# FIDO2AUTH_001.net
KiCad netlist of a schematic drawn in EAGLE
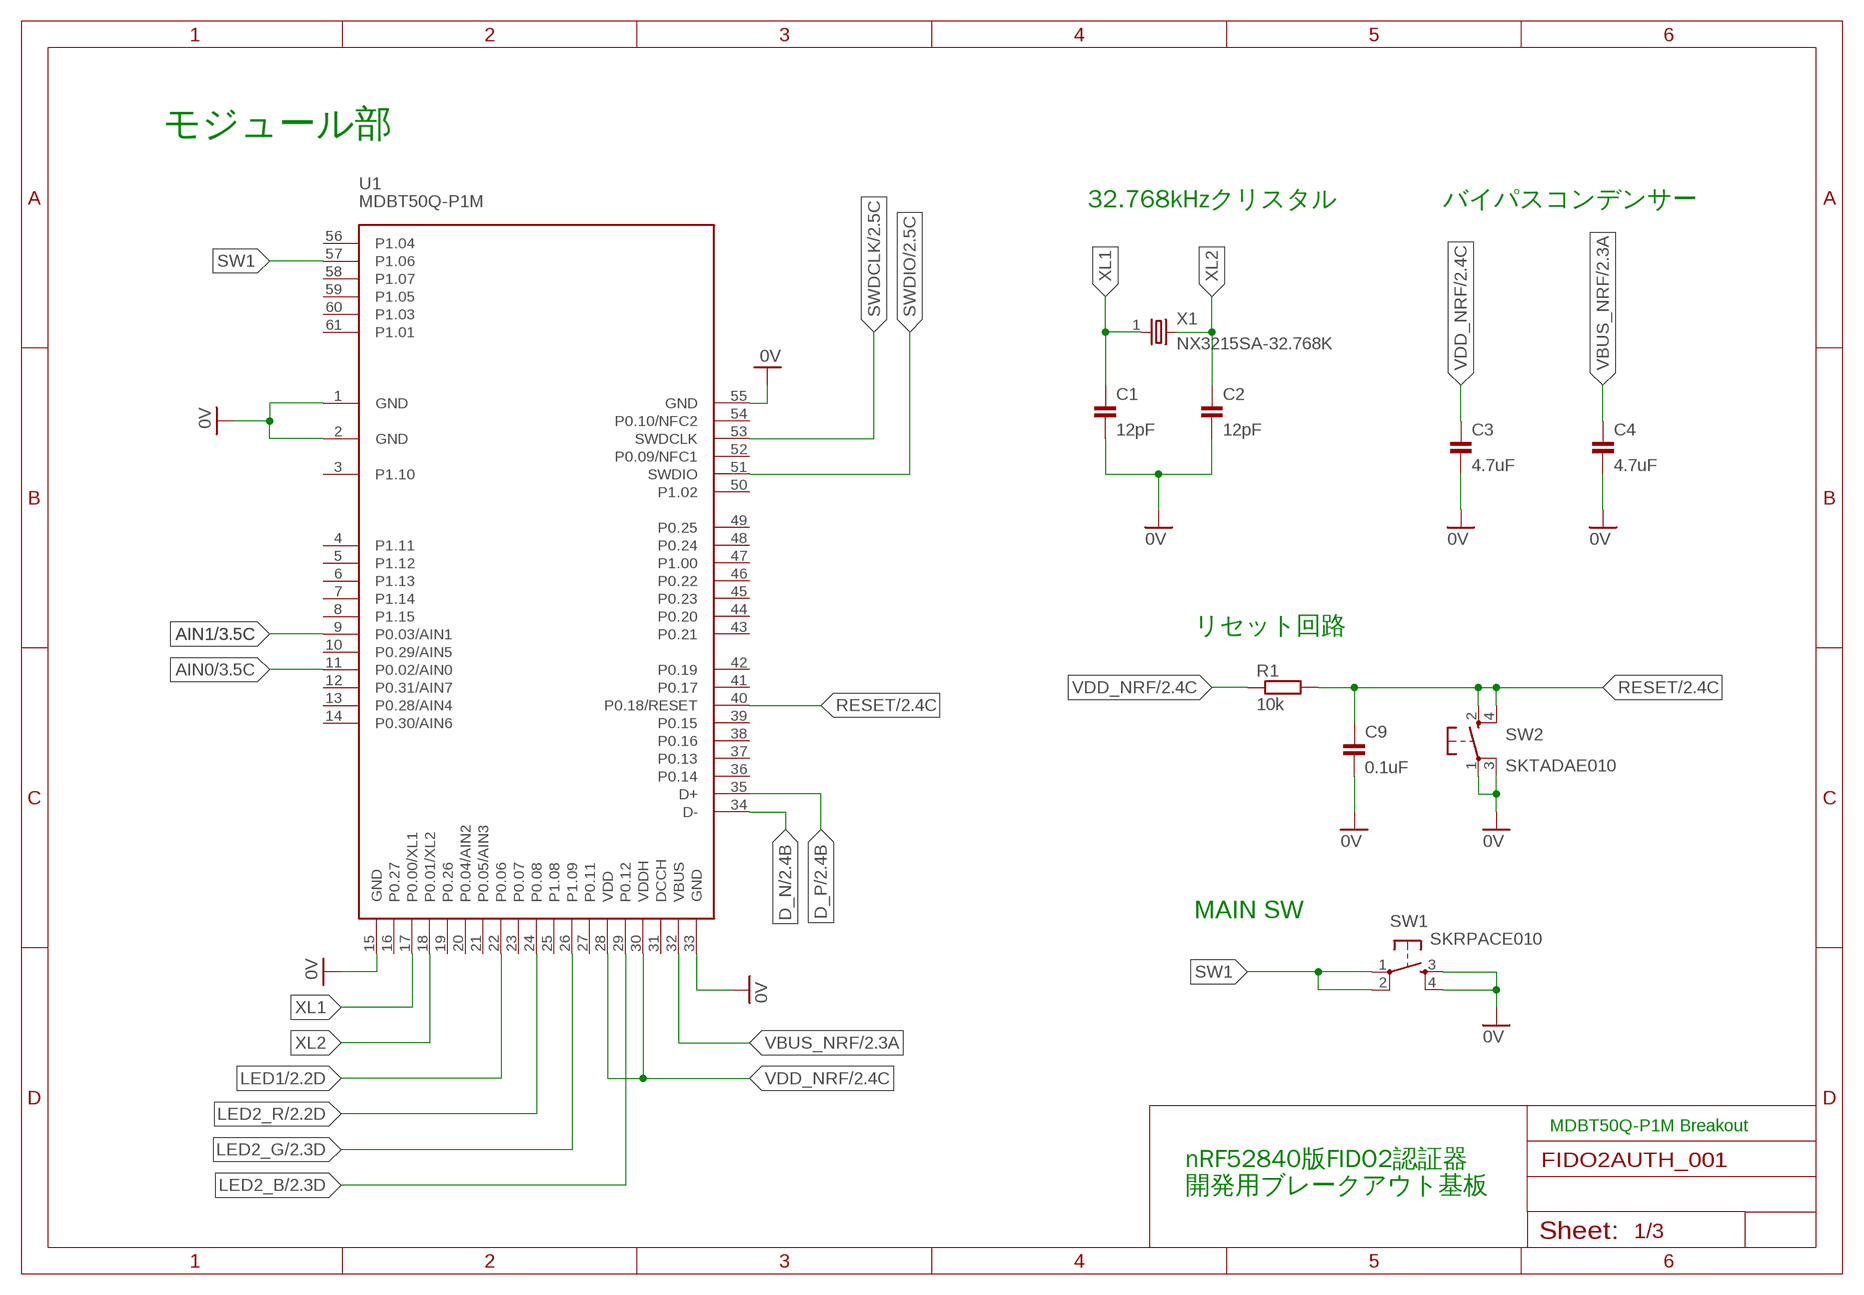
[diagram p0: schematic, sheet 1]
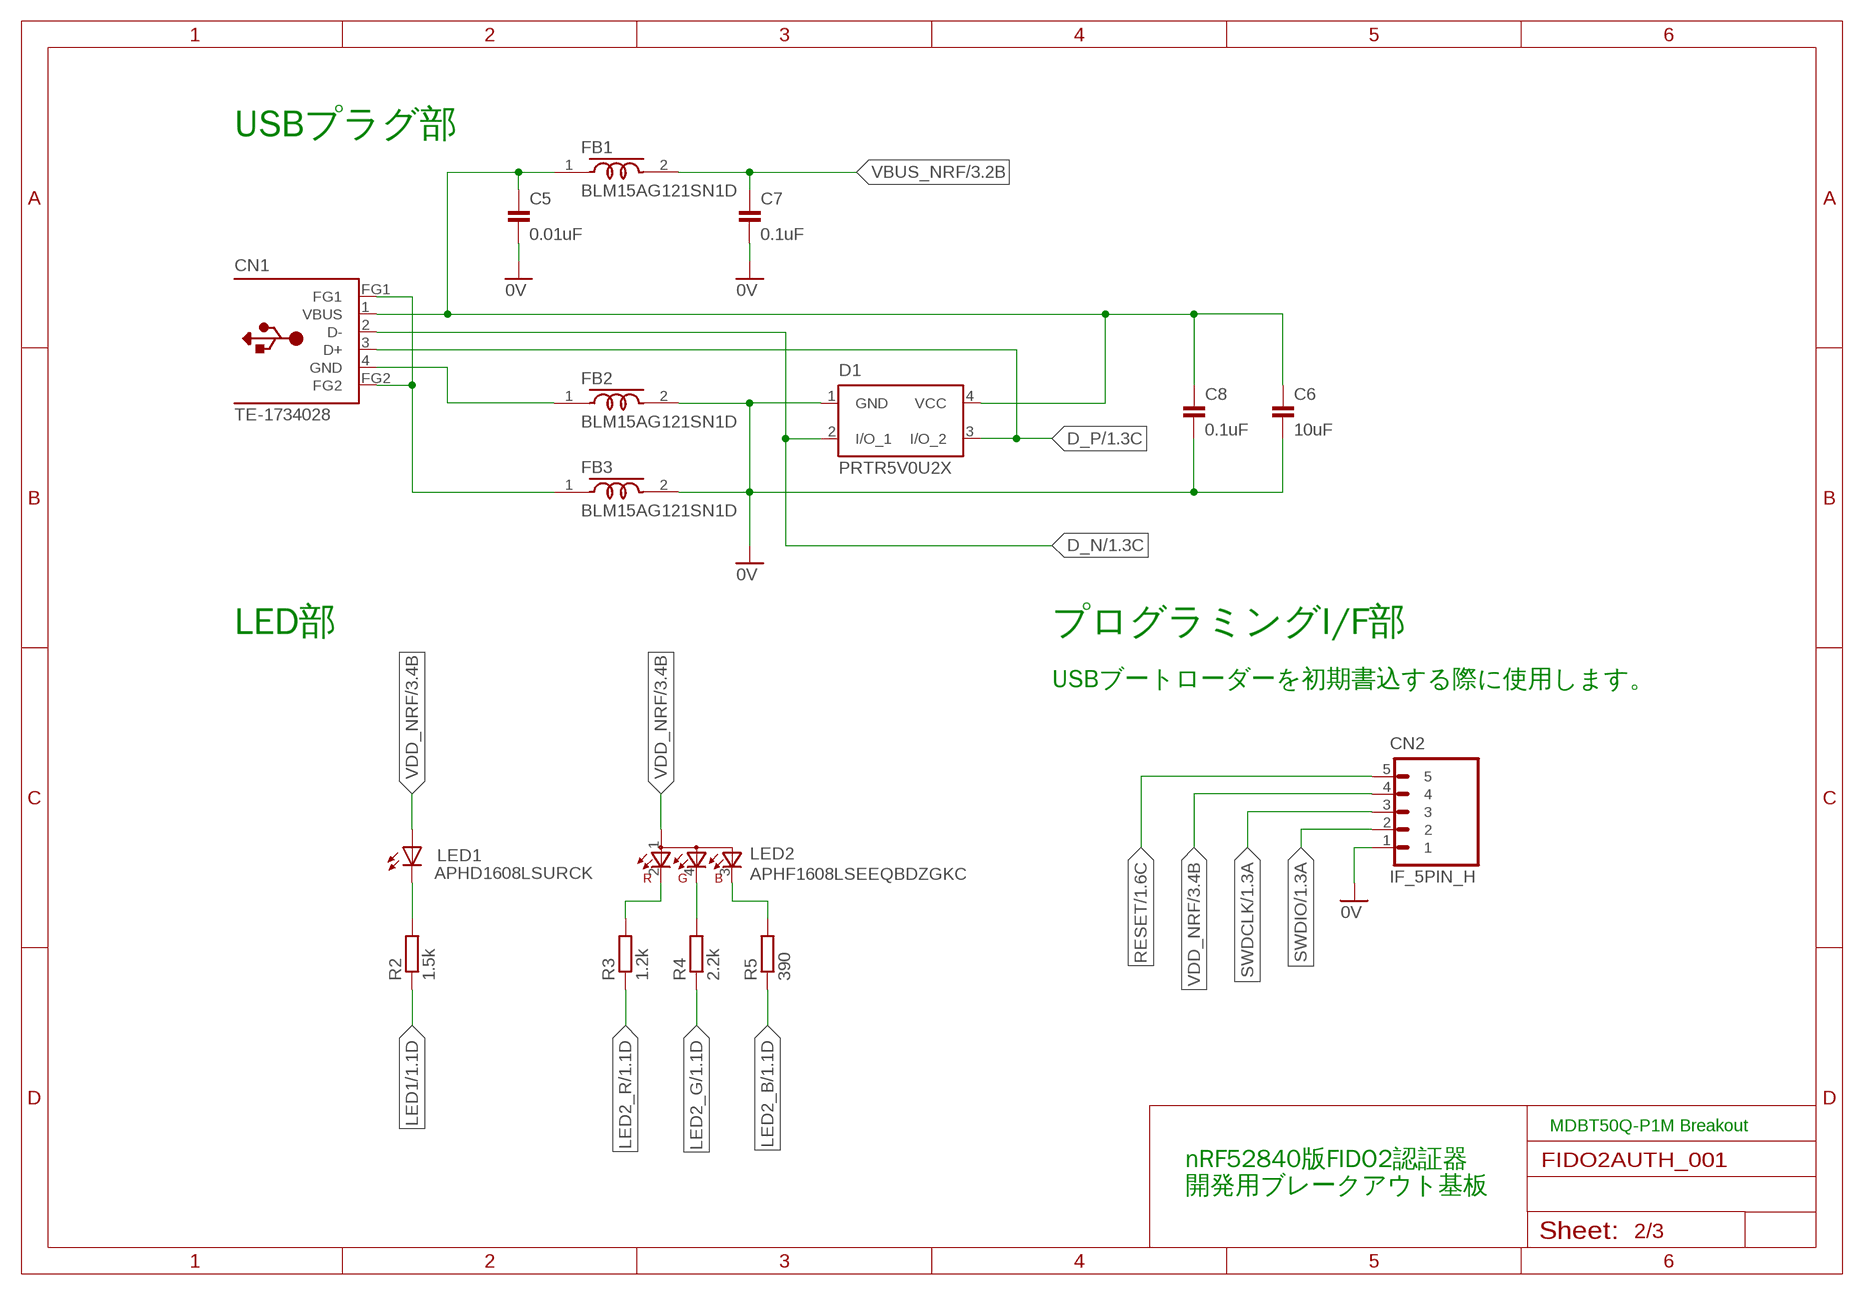
[diagram p1: schematic, sheet 2]
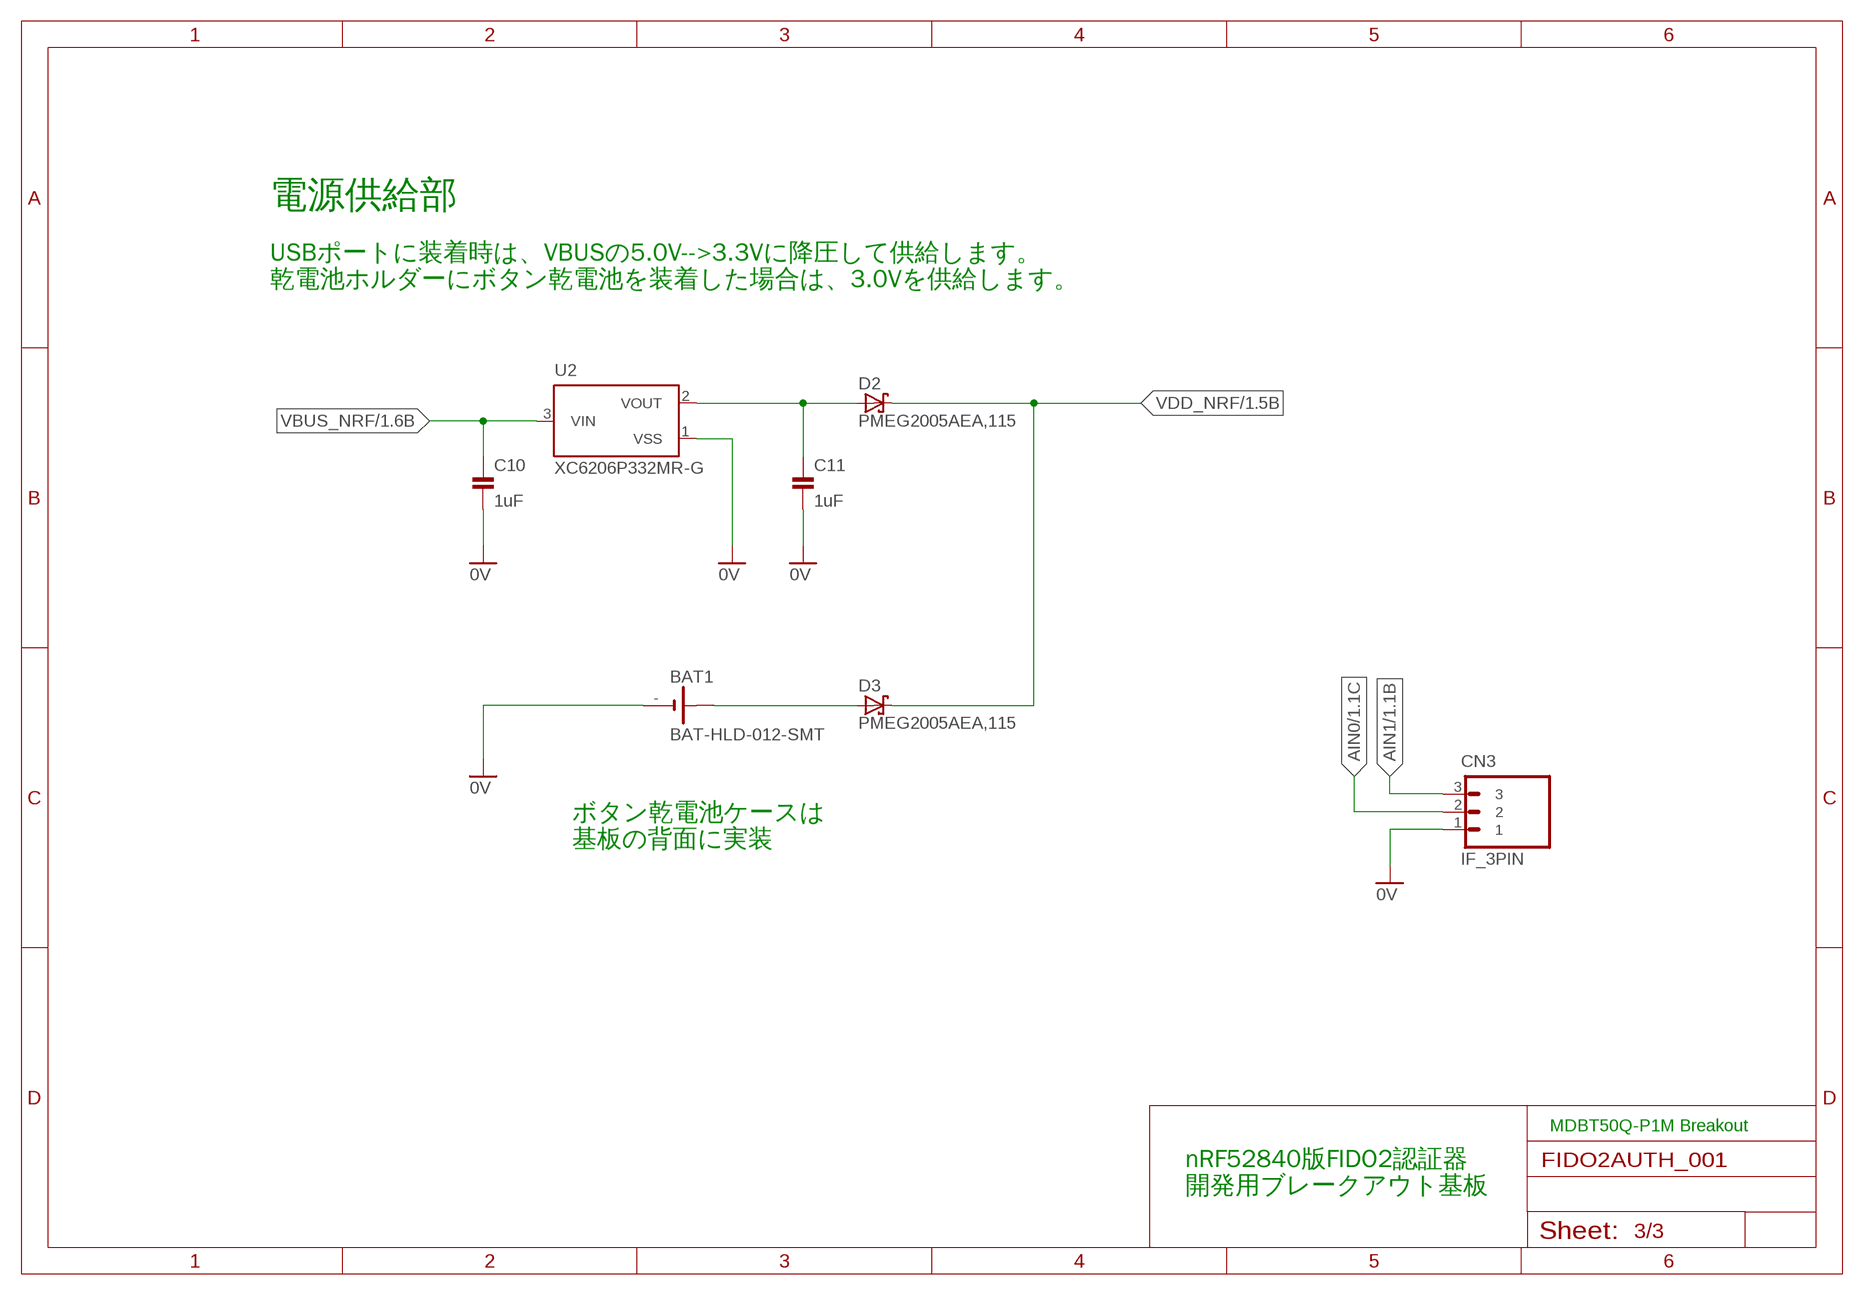
[diagram p2: schematic, sheet 3]

(export (version "E")
  (design (tool "Eeschema 10.0.6"))
  (components
    (comp (ref "C1")
      (value "12pF")
      (footprint "eagle-import:C0603K")
      (libsource (lib "eagle-import") (part "CAP_0603"))
    )
    (comp (ref "C2")
      (value "12pF")
      (footprint "eagle-import:C0603K")
      (libsource (lib "eagle-import") (part "CAP_0603"))
    )
    (comp (ref "C3")
      (value "4.7uF")
      (footprint "eagle-import:C0603K")
      (libsource (lib "eagle-import") (part "CAP_0603"))
    )
    (comp (ref "C4")
      (value "4.7uF")
      (footprint "eagle-import:C0603K")
      (libsource (lib "eagle-import") (part "CAP_0603"))
    )
    (comp (ref "C9")
      (value "0.1uF")
      (footprint "eagle-import:C0603K")
      (libsource (lib "eagle-import") (part "CAP_0603"))
    )
    (comp (ref "R1")
      (value "10k")
      (footprint "eagle-import:R0603")
      (libsource (lib "eagle-import") (part "RESISTOR_0603"))
    )
    (comp (ref "SW1")
      (value "SKRPACE010")
      (footprint "eagle-import:SKRPACE010")
      (libsource (lib "eagle-import") (part "SKRPACE010"))
    )
    (comp (ref "SW2")
      (value "SKTADAE010")
      (footprint "eagle-import:SKTADAE010")
      (libsource (lib "eagle-import") (part "SKTADAE010"))
    )
    (comp (ref "U1")
      (value "MDBT50Q-P1M")
      (footprint "eagle-import:MDBT50Q-P1M")
      (libsource (lib "eagle-import") (part "MDBT50Q-P1M"))
    )
    (comp (ref "X1")
      (value "NX3215SA-32.768K")
      (footprint "eagle-import:NX3215")
      (libsource (lib "eagle-import") (part "NX3215SA-32.768K"))
    )
    (comp (ref "BAT1")
      (value "BAT-HLD-012-SMT")
      (footprint "eagle-import:BAT-HLD-012-SMT")
      (libsource (lib "eagle-import") (part "BAT-HLD-012-SMT"))
    )
    (comp (ref "C10")
      (value "1uF")
      (footprint "eagle-import:C0603K")
      (libsource (lib "eagle-import") (part "CAP_0603"))
    )
    (comp (ref "C11")
      (value "1uF")
      (footprint "eagle-import:C0603K")
      (libsource (lib "eagle-import") (part "CAP_0603"))
    )
    (comp (ref "CN3")
      (value "IF_3PIN")
      (footprint "eagle-import:HEADER_3PIN")
      (libsource (lib "eagle-import") (part "IF_3PIN"))
    )
    (comp (ref "D2")
      (value "PMEG2005AEA,115")
      (footprint "eagle-import:SOD323-W")
      (libsource (lib "eagle-import") (part "PMEG2005AEA,115"))
    )
    (comp (ref "D3")
      (value "PMEG2005AEA,115")
      (footprint "eagle-import:SOD323-W")
      (libsource (lib "eagle-import") (part "PMEG2005AEA,115"))
    )
    (comp (ref "U2")
      (value "XC6206P332MR-G")
      (footprint "eagle-import:SOT23")
      (libsource (lib "eagle-import") (part "XC6206P332MR-G"))
    )
    (comp (ref "C5")
      (value "0.01uF")
      (footprint "eagle-import:C0603K")
      (libsource (lib "eagle-import") (part "CAP_0603"))
    )
    (comp (ref "C6")
      (value "10uF")
      (footprint "eagle-import:C0603K")
      (libsource (lib "eagle-import") (part "CAP_0603"))
    )
    (comp (ref "C7")
      (value "0.1uF")
      (footprint "eagle-import:C0603K")
      (libsource (lib "eagle-import") (part "CAP_0603"))
    )
    (comp (ref "C8")
      (value "0.1uF")
      (footprint "eagle-import:C0603K")
      (libsource (lib "eagle-import") (part "CAP_0603"))
    )
    (comp (ref "CN1")
      (value "TE-1734028")
      (footprint "eagle-import:TE-1734028")
      (libsource (lib "eagle-import") (part "TE-1734028"))
    )
    (comp (ref "CN2")
      (value "IF_5PIN_H")
      (footprint "eagle-import:HEADER_5PIN")
      (libsource (lib "eagle-import") (part "IF_5PIN_H"))
    )
    (comp (ref "D1")
      (value "PRTR5V0U2X")
      (footprint "eagle-import:SOT143B")
      (libsource (lib "eagle-import") (part "PRTR5V0U2X"))
    )
    (comp (ref "FB1")
      (value "BLM15AG121SN1D")
      (footprint "eagle-import:C0402K@1")
      (libsource (lib "eagle-import") (part "BLM15AG121SN1D"))
    )
    (comp (ref "FB2")
      (value "BLM15AG121SN1D")
      (footprint "eagle-import:C0402K@1")
      (libsource (lib "eagle-import") (part "BLM15AG121SN1D"))
    )
    (comp (ref "FB3")
      (value "BLM15AG121SN1D")
      (footprint "eagle-import:C0402K@1")
      (libsource (lib "eagle-import") (part "BLM15AG121SN1D"))
    )
    (comp (ref "LED1")
      (value "APHD1608LSURCK")
      (footprint "eagle-import:CHIPLED_0603")
      (libsource (lib "eagle-import") (part "APHD1608LSURCK"))
    )
    (comp (ref "LED2")
      (value "APHF1608LSEEQBDZGKC")
      (footprint "eagle-import:APHF1608LSEEQBDZGKC")
      (libsource (lib "eagle-import") (part "APHF1608LSEEQBDZGKC"))
    )
    (comp (ref "R2")
      (value "1.5k")
      (footprint "eagle-import:R0603")
      (libsource (lib "eagle-import") (part "RESISTOR_0603"))
    )
    (comp (ref "R3")
      (value "1.2k")
      (footprint "eagle-import:R0603")
      (libsource (lib "eagle-import") (part "RESISTOR_0603"))
    )
    (comp (ref "R4")
      (value "2.2k")
      (footprint "eagle-import:R0603")
      (libsource (lib "eagle-import") (part "RESISTOR_0603"))
    )
    (comp (ref "R5")
      (value "390")
      (footprint "eagle-import:R0603")
      (libsource (lib "eagle-import") (part "RESISTOR_0603"))
    )
  )
  (nets
    (net (code "1") (name "0V") (class "Default")
      (node (ref "BAT1") (pin "-") (pinfunction "-_-") (pintype "passive"))
      (node (ref "C1") (pin "2") (pinfunction "2_2") (pintype "passive"))
      (node (ref "C10") (pin "2") (pinfunction "2_2") (pintype "passive"))
      (node (ref "C11") (pin "2") (pinfunction "2_2") (pintype "passive"))
      (node (ref "C2") (pin "2") (pinfunction "2_2") (pintype "passive"))
      (node (ref "C3") (pin "2") (pinfunction "2_2") (pintype "passive"))
      (node (ref "C4") (pin "2") (pinfunction "2_2") (pintype "passive"))
      (node (ref "C5") (pin "2") (pinfunction "2_2") (pintype "passive"))
      (node (ref "C6") (pin "2") (pinfunction "2_2") (pintype "passive"))
      (node (ref "C7") (pin "2") (pinfunction "2_2") (pintype "passive"))
      (node (ref "C8") (pin "2") (pinfunction "2_2") (pintype "passive"))
      (node (ref "C9") (pin "2") (pinfunction "2_2") (pintype "passive"))
      (node (ref "CN2") (pin "1") (pinfunction "1_1") (pintype "passive"))
      (node (ref "CN3") (pin "1") (pinfunction "1_1") (pintype "passive"))
      (node (ref "D1") (pin "1") (pinfunction "GND_1") (pintype "passive"))
      (node (ref "FB2") (pin "2") (pinfunction "2_2") (pintype "passive"))
      (node (ref "FB3") (pin "2") (pinfunction "2_2") (pintype "passive"))
      (node (ref "SW1") (pin "3") (pinfunction "S_3") (pintype "passive"))
      (node (ref "SW1") (pin "4") (pinfunction "S1_4") (pintype "passive"))
      (node (ref "SW2") (pin "1") (pinfunction "P_1") (pintype "passive"))
      (node (ref "SW2") (pin "3") (pinfunction "P1_3") (pintype "passive"))
      (node (ref "U1") (pin "1") (pinfunction "GND_1") (pintype "bidirectional"))
      (node (ref "U1") (pin "15") (pinfunction "GND_15") (pintype "bidirectional"))
      (node (ref "U1") (pin "2") (pinfunction "GND_2") (pintype "bidirectional"))
      (node (ref "U1") (pin "33") (pinfunction "GND_33") (pintype "bidirectional"))
      (node (ref "U1") (pin "55") (pinfunction "GND_55") (pintype "bidirectional"))
      (node (ref "U2") (pin "1") (pinfunction "VSS_1") (pintype "passive"))
    )
    (net (code "2") (name "AIN0") (class "Default")
      (node (ref "CN3") (pin "2") (pinfunction "2_2") (pintype "passive"))
      (node (ref "U1") (pin "11") (pinfunction "P0.02/AIN0_11") (pintype "bidirectional"))
    )
    (net (code "3") (name "AIN1") (class "Default")
      (node (ref "CN3") (pin "3") (pinfunction "3_3") (pintype "passive"))
      (node (ref "U1") (pin "9") (pinfunction "P0.03/AIN1_9") (pintype "bidirectional"))
    )
    (net (code "4") (name "D_N") (class "Default")
      (node (ref "CN1") (pin "2") (pinfunction "D-_2") (pintype "bidirectional"))
      (node (ref "D1") (pin "2") (pinfunction "I/O_1_2") (pintype "bidirectional"))
      (node (ref "U1") (pin "34") (pinfunction "D-_34") (pintype "bidirectional"))
    )
    (net (code "5") (name "D_P") (class "Default")
      (node (ref "CN1") (pin "3") (pinfunction "D+_3") (pintype "bidirectional"))
      (node (ref "D1") (pin "3") (pinfunction "I/O_2_3") (pintype "bidirectional"))
      (node (ref "U1") (pin "35") (pinfunction "D+_35") (pintype "bidirectional"))
    )
    (net (code "6") (name "LED1") (class "Default")
      (node (ref "R2") (pin "1") (pinfunction "1_1") (pintype "passive"))
      (node (ref "U1") (pin "22") (pinfunction "P0.06_22") (pintype "bidirectional"))
    )
    (net (code "7") (name "LED2_B") (class "Default")
      (node (ref "R5") (pin "1") (pinfunction "1_1") (pintype "passive"))
      (node (ref "U1") (pin "29") (pinfunction "P0.12_29") (pintype "bidirectional"))
    )
    (net (code "8") (name "LED2_G") (class "Default")
      (node (ref "R4") (pin "1") (pinfunction "1_1") (pintype "passive"))
      (node (ref "U1") (pin "26") (pinfunction "P1.09_26") (pintype "bidirectional"))
    )
    (net (code "9") (name "LED2_R") (class "Default")
      (node (ref "R3") (pin "1") (pinfunction "1_1") (pintype "passive"))
      (node (ref "U1") (pin "24") (pinfunction "P0.08_24") (pintype "bidirectional"))
    )
    (net (code "10") (name "Net-(BAT1-+)") (class "Default")
      (node (ref "BAT1") (pin "+@1") (pinfunction "+_+@1") (pintype "passive"))
      (node (ref "D3") (pin "A") (pinfunction "A_A") (pintype "passive"))
    )
    (net (code "11") (name "Net-(CN1-GND)") (class "Default")
      (node (ref "CN1") (pin "4") (pinfunction "GND_4") (pintype "passive"))
      (node (ref "FB2") (pin "1") (pinfunction "1_1") (pintype "passive"))
    )
    (net (code "12") (name "Net-(CN1-PadFG1)") (class "Default")
      (node (ref "CN1") (pin "FG1") (pinfunction "FG1_FG1") (pintype "passive"))
      (node (ref "CN1") (pin "FG2") (pinfunction "FG2_FG2") (pintype "passive"))
      (node (ref "FB3") (pin "1") (pinfunction "1_1") (pintype "passive"))
    )
    (net (code "13") (name "Net-(CN1-VBUS)") (class "Default")
      (node (ref "C5") (pin "1") (pinfunction "1_1") (pintype "passive"))
      (node (ref "C6") (pin "1") (pinfunction "1_1") (pintype "passive"))
      (node (ref "C8") (pin "1") (pinfunction "1_1") (pintype "passive"))
      (node (ref "CN1") (pin "1") (pinfunction "VBUS_1") (pintype "passive"))
      (node (ref "D1") (pin "4") (pinfunction "VCC_4") (pintype "passive"))
      (node (ref "FB1") (pin "1") (pinfunction "1_1") (pintype "passive"))
    )
    (net (code "14") (name "Net-(LED1-PadC)") (class "Default")
      (node (ref "LED1") (pin "C") (pinfunction "C_C") (pintype "passive"))
      (node (ref "R2") (pin "2") (pinfunction "2_2") (pintype "passive"))
    )
    (net (code "15") (name "Net-(LED2-CBLUE)") (class "Default")
      (node (ref "LED2") (pin "3") (pinfunction "CBLUE_3") (pintype "passive"))
      (node (ref "R5") (pin "2") (pinfunction "2_2") (pintype "passive"))
    )
    (net (code "16") (name "Net-(LED2-CGREEN)") (class "Default")
      (node (ref "LED2") (pin "4") (pinfunction "CGREEN_4") (pintype "passive"))
      (node (ref "R4") (pin "2") (pinfunction "2_2") (pintype "passive"))
    )
    (net (code "17") (name "Net-(LED2-CRED)") (class "Default")
      (node (ref "LED2") (pin "2") (pinfunction "CRED_2") (pintype "passive"))
      (node (ref "R3") (pin "2") (pinfunction "2_2") (pintype "passive"))
    )
    (net (code "18") (name "Net-(U2-VOUT)") (class "Default")
      (node (ref "C11") (pin "1") (pinfunction "1_1") (pintype "passive"))
      (node (ref "D2") (pin "A") (pinfunction "A_A") (pintype "passive"))
      (node (ref "U2") (pin "2") (pinfunction "VOUT_2") (pintype "passive"))
    )
    (net (code "19") (name "RESET") (class "Default")
      (node (ref "C9") (pin "1") (pinfunction "1_1") (pintype "passive"))
      (node (ref "CN2") (pin "5") (pinfunction "5_5") (pintype "passive"))
      (node (ref "R1") (pin "2") (pinfunction "2_2") (pintype "passive"))
      (node (ref "SW2") (pin "2") (pinfunction "S_2") (pintype "passive"))
      (node (ref "SW2") (pin "4") (pinfunction "S1_4") (pintype "passive"))
      (node (ref "U1") (pin "40") (pinfunction "P0.18/RESET_40") (pintype "bidirectional"))
    )
    (net (code "20") (name "SW1") (class "Default")
      (node (ref "SW1") (pin "1") (pinfunction "P_1") (pintype "passive"))
      (node (ref "SW1") (pin "2") (pinfunction "P1_2") (pintype "passive"))
      (node (ref "U1") (pin "57") (pinfunction "P1.06_57") (pintype "bidirectional"))
    )
    (net (code "21") (name "SWDCLK") (class "Default")
      (node (ref "CN2") (pin "3") (pinfunction "3_3") (pintype "passive"))
      (node (ref "U1") (pin "53") (pinfunction "SWDCLK_53") (pintype "bidirectional"))
    )
    (net (code "22") (name "SWDIO") (class "Default")
      (node (ref "CN2") (pin "2") (pinfunction "2_2") (pintype "passive"))
      (node (ref "U1") (pin "51") (pinfunction "SWDIO_51") (pintype "bidirectional"))
    )
    (net (code "23") (name "VBUS_NRF") (class "Default")
      (node (ref "C10") (pin "1") (pinfunction "1_1") (pintype "passive"))
      (node (ref "C4") (pin "1") (pinfunction "1_1") (pintype "passive"))
      (node (ref "C7") (pin "1") (pinfunction "1_1") (pintype "passive"))
      (node (ref "FB1") (pin "2") (pinfunction "2_2") (pintype "passive"))
      (node (ref "U1") (pin "32") (pinfunction "VBUS_32") (pintype "bidirectional"))
      (node (ref "U2") (pin "3") (pinfunction "VIN_3") (pintype "passive"))
    )
    (net (code "24") (name "VDD_NRF") (class "Default")
      (node (ref "C3") (pin "1") (pinfunction "1_1") (pintype "passive"))
      (node (ref "CN2") (pin "4") (pinfunction "4_4") (pintype "passive"))
      (node (ref "D2") (pin "C") (pinfunction "C_C") (pintype "passive"))
      (node (ref "D3") (pin "C") (pinfunction "C_C") (pintype "passive"))
      (node (ref "LED1") (pin "A") (pinfunction "A_A") (pintype "passive"))
      (node (ref "LED2") (pin "1") (pinfunction "A_1") (pintype "passive"))
      (node (ref "R1") (pin "1") (pinfunction "1_1") (pintype "passive"))
      (node (ref "U1") (pin "28") (pinfunction "VDD_28") (pintype "bidirectional"))
      (node (ref "U1") (pin "30") (pinfunction "VDDH_30") (pintype "bidirectional"))
    )
    (net (code "25") (name "XL1") (class "Default")
      (node (ref "C1") (pin "1") (pinfunction "1_1") (pintype "passive"))
      (node (ref "U1") (pin "17") (pinfunction "P0.00/XL1_17") (pintype "bidirectional"))
      (node (ref "X1") (pin "1") (pinfunction "1_1") (pintype "passive"))
    )
    (net (code "26") (name "XL2") (class "Default")
      (node (ref "C2") (pin "1") (pinfunction "1_1") (pintype "passive"))
      (node (ref "U1") (pin "18") (pinfunction "P0.01/XL2_18") (pintype "bidirectional"))
      (node (ref "X1") (pin "2") (pinfunction "2_2") (pintype "passive"))
    )
    (net (code "27") (name "unconnected-(U1-DCCH-Pad31)") (class "Default")
      (node (ref "U1") (pin "31") (pinfunction "DCCH_31") (pintype "bidirectional"))
    )
    (net (code "28") (name "unconnected-(U1-P0.04{slash}AIN2-Pad20)") (class "Default")
      (node (ref "U1") (pin "20") (pinfunction "P0.04/AIN2_20") (pintype "bidirectional"))
    )
    (net (code "29") (name "unconnected-(U1-P0.05{slash}AIN3-Pad21)") (class "Default")
      (node (ref "U1") (pin "21") (pinfunction "P0.05/AIN3_21") (pintype "bidirectional"))
    )
    (net (code "30") (name "unconnected-(U1-P0.07-Pad23)") (class "Default")
      (node (ref "U1") (pin "23") (pinfunction "P0.07_23") (pintype "bidirectional"))
    )
    (net (code "31") (name "unconnected-(U1-P0.09{slash}NFC1-Pad52)") (class "Default")
      (node (ref "U1") (pin "52") (pinfunction "P0.09/NFC1_52") (pintype "bidirectional"))
    )
    (net (code "32") (name "unconnected-(U1-P0.10{slash}NFC2-Pad54)") (class "Default")
      (node (ref "U1") (pin "54") (pinfunction "P0.10/NFC2_54") (pintype "bidirectional"))
    )
    (net (code "33") (name "unconnected-(U1-P0.11-Pad27)") (class "Default")
      (node (ref "U1") (pin "27") (pinfunction "P0.11_27") (pintype "bidirectional"))
    )
    (net (code "34") (name "unconnected-(U1-P0.13-Pad37)") (class "Default")
      (node (ref "U1") (pin "37") (pinfunction "P0.13_37") (pintype "bidirectional"))
    )
    (net (code "35") (name "unconnected-(U1-P0.14-Pad36)") (class "Default")
      (node (ref "U1") (pin "36") (pinfunction "P0.14_36") (pintype "bidirectional"))
    )
    (net (code "36") (name "unconnected-(U1-P0.15-Pad39)") (class "Default")
      (node (ref "U1") (pin "39") (pinfunction "P0.15_39") (pintype "bidirectional"))
    )
    (net (code "37") (name "unconnected-(U1-P0.16-Pad38)") (class "Default")
      (node (ref "U1") (pin "38") (pinfunction "P0.16_38") (pintype "bidirectional"))
    )
    (net (code "38") (name "unconnected-(U1-P0.17-Pad41)") (class "Default")
      (node (ref "U1") (pin "41") (pinfunction "P0.17_41") (pintype "bidirectional"))
    )
    (net (code "39") (name "unconnected-(U1-P0.19-Pad42)") (class "Default")
      (node (ref "U1") (pin "42") (pinfunction "P0.19_42") (pintype "bidirectional"))
    )
    (net (code "40") (name "unconnected-(U1-P0.20-Pad44)") (class "Default")
      (node (ref "U1") (pin "44") (pinfunction "P0.20_44") (pintype "bidirectional"))
    )
    (net (code "41") (name "unconnected-(U1-P0.21-Pad43)") (class "Default")
      (node (ref "U1") (pin "43") (pinfunction "P0.21_43") (pintype "bidirectional"))
    )
    (net (code "42") (name "unconnected-(U1-P0.22-Pad46)") (class "Default")
      (node (ref "U1") (pin "46") (pinfunction "P0.22_46") (pintype "bidirectional"))
    )
    (net (code "43") (name "unconnected-(U1-P0.23-Pad45)") (class "Default")
      (node (ref "U1") (pin "45") (pinfunction "P0.23_45") (pintype "bidirectional"))
    )
    (net (code "44") (name "unconnected-(U1-P0.24-Pad48)") (class "Default")
      (node (ref "U1") (pin "48") (pinfunction "P0.24_48") (pintype "bidirectional"))
    )
    (net (code "45") (name "unconnected-(U1-P0.25-Pad49)") (class "Default")
      (node (ref "U1") (pin "49") (pinfunction "P0.25_49") (pintype "bidirectional"))
    )
    (net (code "46") (name "unconnected-(U1-P0.26-Pad19)") (class "Default")
      (node (ref "U1") (pin "19") (pinfunction "P0.26_19") (pintype "bidirectional"))
    )
    (net (code "47") (name "unconnected-(U1-P0.27-Pad16)") (class "Default")
      (node (ref "U1") (pin "16") (pinfunction "P0.27_16") (pintype "bidirectional"))
    )
    (net (code "48") (name "unconnected-(U1-P0.28{slash}AIN4-Pad13)") (class "Default")
      (node (ref "U1") (pin "13") (pinfunction "P0.28/AIN4_13") (pintype "bidirectional"))
    )
    (net (code "49") (name "unconnected-(U1-P0.29{slash}AIN5-Pad10)") (class "Default")
      (node (ref "U1") (pin "10") (pinfunction "P0.29/AIN5_10") (pintype "bidirectional"))
    )
    (net (code "50") (name "unconnected-(U1-P0.30{slash}AIN6-Pad14)") (class "Default")
      (node (ref "U1") (pin "14") (pinfunction "P0.30/AIN6_14") (pintype "bidirectional"))
    )
    (net (code "51") (name "unconnected-(U1-P0.31{slash}AIN7-Pad12)") (class "Default")
      (node (ref "U1") (pin "12") (pinfunction "P0.31/AIN7_12") (pintype "bidirectional"))
    )
    (net (code "52") (name "unconnected-(U1-P1.00-Pad47)") (class "Default")
      (node (ref "U1") (pin "47") (pinfunction "P1.00_47") (pintype "bidirectional"))
    )
    (net (code "53") (name "unconnected-(U1-P1.01-Pad61)") (class "Default")
      (node (ref "U1") (pin "61") (pinfunction "P1.01_61") (pintype "bidirectional"))
    )
    (net (code "54") (name "unconnected-(U1-P1.02-Pad50)") (class "Default")
      (node (ref "U1") (pin "50") (pinfunction "P1.02_50") (pintype "bidirectional"))
    )
    (net (code "55") (name "unconnected-(U1-P1.03-Pad60)") (class "Default")
      (node (ref "U1") (pin "60") (pinfunction "P1.03_60") (pintype "bidirectional"))
    )
    (net (code "56") (name "unconnected-(U1-P1.04-Pad56)") (class "Default")
      (node (ref "U1") (pin "56") (pinfunction "P1.04_56") (pintype "bidirectional"))
    )
    (net (code "57") (name "unconnected-(U1-P1.05-Pad59)") (class "Default")
      (node (ref "U1") (pin "59") (pinfunction "P1.05_59") (pintype "bidirectional"))
    )
    (net (code "58") (name "unconnected-(U1-P1.07-Pad58)") (class "Default")
      (node (ref "U1") (pin "58") (pinfunction "P1.07_58") (pintype "bidirectional"))
    )
    (net (code "59") (name "unconnected-(U1-P1.08-Pad25)") (class "Default")
      (node (ref "U1") (pin "25") (pinfunction "P1.08_25") (pintype "bidirectional"))
    )
    (net (code "60") (name "unconnected-(U1-P1.10-Pad3)") (class "Default")
      (node (ref "U1") (pin "3") (pinfunction "P1.10_3") (pintype "bidirectional"))
    )
    (net (code "61") (name "unconnected-(U1-P1.11-Pad4)") (class "Default")
      (node (ref "U1") (pin "4") (pinfunction "P1.11_4") (pintype "bidirectional"))
    )
    (net (code "62") (name "unconnected-(U1-P1.12-Pad5)") (class "Default")
      (node (ref "U1") (pin "5") (pinfunction "P1.12_5") (pintype "bidirectional"))
    )
    (net (code "63") (name "unconnected-(U1-P1.13-Pad6)") (class "Default")
      (node (ref "U1") (pin "6") (pinfunction "P1.13_6") (pintype "bidirectional"))
    )
    (net (code "64") (name "unconnected-(U1-P1.14-Pad7)") (class "Default")
      (node (ref "U1") (pin "7") (pinfunction "P1.14_7") (pintype "bidirectional"))
    )
    (net (code "65") (name "unconnected-(U1-P1.15-Pad8)") (class "Default")
      (node (ref "U1") (pin "8") (pinfunction "P1.15_8") (pintype "bidirectional"))
    )
  )
)
